# Microprocessor1.net
KiCad netlist of a schematic drawn in Altium Designer
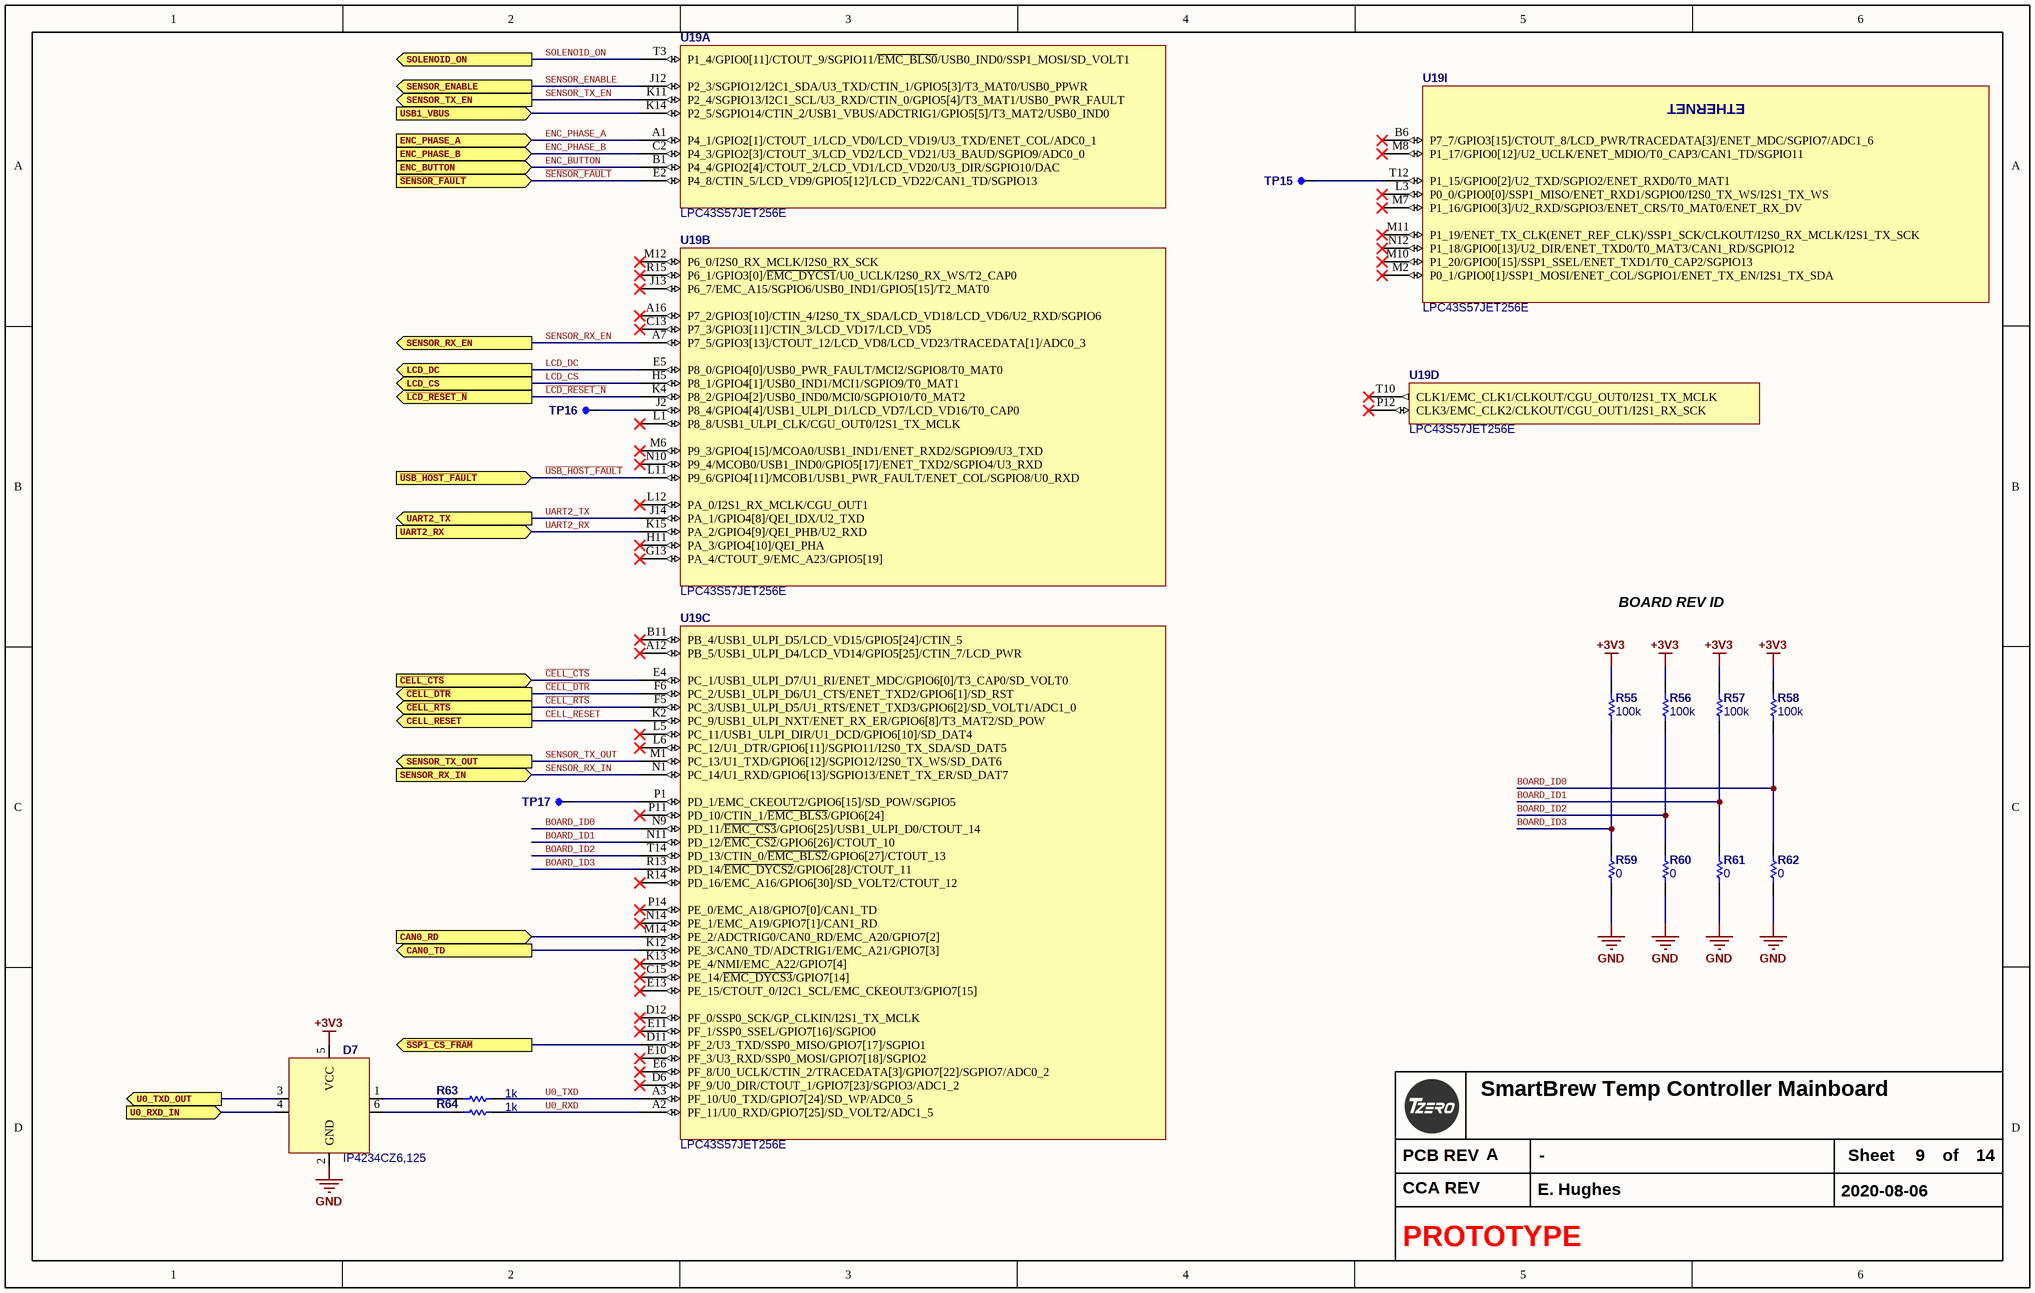
[diagram p0: Microprocessor1.SchDoc]

(export (version "E")
  (design (tool "Eeschema 10.0.6"))
  (components
    (comp (ref "D7")
      (value "IP4234CZ6,125")
      (footprint "SOT427_MEDIUM")
      (description "IC USB2.0 ESD PROTECTION SOT457")
      (fields (field (name "MANUFACTURER") "NXP Semiconductors"))
      (libsource (lib "Diodes-N") (part "IP4234CZ6,125"))
    )
    (comp (ref "R55")
      (value "100k")
      (footprint "R0603_0.55MM_MD")
      (description "RES 100K OHM 1/10W 1% 0603 SMD")
      (fields
        (field (name "MANUFACTURER PART NUMBER") "ERJ-3EKF1003V")
        (field (name "MANUFACTURER") "Panasonic Electronic Components")
      )
      (libsource (lib "Resistors - Panasonic - AEC-Q200") (part "R_2P"))
    )
    (comp (ref "R56")
      (value "100k")
      (footprint "R0603_0.55MM_MD")
      (description "RES 100K OHM 1/10W 1% 0603 SMD")
      (fields
        (field (name "MANUFACTURER PART NUMBER") "ERJ-3EKF1003V")
        (field (name "MANUFACTURER") "Panasonic Electronic Components")
      )
      (libsource (lib "Resistors - Panasonic - AEC-Q200") (part "R_2P"))
    )
    (comp (ref "R57")
      (value "100k")
      (footprint "R0603_0.55MM_MD")
      (description "RES 100K OHM 1/10W 1% 0603 SMD")
      (fields
        (field (name "MANUFACTURER PART NUMBER") "ERJ-3EKF1003V")
        (field (name "MANUFACTURER") "Panasonic Electronic Components")
      )
      (libsource (lib "Resistors - Panasonic - AEC-Q200") (part "R_2P"))
    )
    (comp (ref "R58")
      (value "100k")
      (footprint "R0603_0.55MM_MD")
      (description "RES 100K OHM 1/10W 1% 0603 SMD")
      (fields
        (field (name "MANUFACTURER PART NUMBER") "ERJ-3EKF1003V")
        (field (name "MANUFACTURER") "Panasonic Electronic Components")
      )
      (libsource (lib "Resistors - Panasonic - AEC-Q200") (part "R_2P"))
    )
    (comp (ref "R59")
      (value "0")
      (footprint "R0603_0.55MM_MD")
      (description "RES 0.0 OHM 1/10W JUMP 0603 SMD")
      (fields
        (field (name "MANUFACTURER") "Panasonic Electronic Components")
        (field (name "MANUFACTURER PART NUMBER") "ERJ-3GEY0R00V")
      )
      (libsource (lib "Resistors - Panasonic - AEC-Q200") (part "R_2P"))
    )
    (comp (ref "R60")
      (value "0")
      (footprint "R0603_0.55MM_MD")
      (description "RES 0.0 OHM 1/10W JUMP 0603 SMD")
      (fields
        (field (name "MANUFACTURER") "Panasonic Electronic Components")
        (field (name "MANUFACTURER PART NUMBER") "ERJ-3GEY0R00V")
      )
      (libsource (lib "Resistors - Panasonic - AEC-Q200") (part "R_2P"))
    )
    (comp (ref "R61")
      (value "0")
      (footprint "R0603_0.55MM_MD")
      (description "RES 0.0 OHM 1/10W JUMP 0603 SMD")
      (fields
        (field (name "MANUFACTURER") "Panasonic Electronic Components")
        (field (name "MANUFACTURER PART NUMBER") "ERJ-3GEY0R00V")
      )
      (libsource (lib "Resistors - Panasonic - AEC-Q200") (part "R_2P"))
    )
    (comp (ref "R62")
      (value "0")
      (footprint "R0603_0.55MM_MD")
      (description "RES 0.0 OHM 1/10W JUMP 0603 SMD")
      (fields
        (field (name "MANUFACTURER") "Panasonic Electronic Components")
        (field (name "MANUFACTURER PART NUMBER") "ERJ-3GEY0R00V")
      )
      (libsource (lib "Resistors - Panasonic - AEC-Q200") (part "R_2P"))
    )
    (comp (ref "R63")
      (value "1k")
      (footprint "R0603_0.55MM_MD")
      (description "RES 1K OHM 1/10W 1% 0603 SMD")
      (fields
        (field (name "MANUFACTURER PART NUMBER") "ERJ-3EKF1001V")
        (field (name "MANUFACTURER") "Panasonic Electronic Components")
      )
      (libsource (lib "Resistors - Panasonic - AEC-Q200") (part "R_2P"))
    )
    (comp (ref "R64")
      (value "1k")
      (footprint "R0603_0.55MM_MD")
      (description "RES 1K OHM 1/10W 1% 0603 SMD")
      (fields
        (field (name "MANUFACTURER PART NUMBER") "ERJ-3EKF1001V")
        (field (name "MANUFACTURER") "Panasonic Electronic Components")
      )
      (libsource (lib "Resistors - Panasonic - AEC-Q200") (part "R_2P"))
    )
    (comp (ref "TP15")
      (value "~")
      (footprint "TP_SMT_25_MIL_ROUND")
      (libsource (lib "Test Points-N") (part "TP SMT 25MIL"))
    )
    (comp (ref "TP16")
      (value "~")
      (footprint "TP_SMT_25_MIL_ROUND")
      (libsource (lib "Test Points-N") (part "TP SMT 25MIL"))
    )
    (comp (ref "TP17")
      (value "~")
      (footprint "TP_SMT_25_MIL_ROUND")
      (libsource (lib "Test Points-N") (part "TP SMT 25MIL"))
    )
    (comp (ref "U19")
      (value "LPC43S57JET256E")
      (footprint "Integrated Circuits BGA-N:LBGA256 16X16 1700X1700X155")
      (description "ARM Microcontrollers - MCU CortexM0/4 32bit 1MB Cortex-M4/M0")
      (fields (field (name "MANUFACTURER") "NXP Semiconductors"))
      (libsource (lib "eIC") (part "LPC43S57JET256E"))
    )
  )
  (nets
    (net (code "1") (name "+3V3") (class "Default")
      (node (ref "D7") (pin "5") (pinfunction "VCC_5") (pintype "passive"))
      (node (ref "R55") (pin "1") (pinfunction "1_1") (pintype "passive"))
      (node (ref "R56") (pin "1") (pinfunction "1_1") (pintype "passive"))
      (node (ref "R57") (pin "1") (pinfunction "1_1") (pintype "passive"))
      (node (ref "R58") (pin "1") (pinfunction "1_1") (pintype "passive"))
    )
    (net (code "2") (name "/BOARD_ID0") (class "Default")
      (node (ref "R58") (pin "2") (pinfunction "2_2") (pintype "passive"))
      (node (ref "R62") (pin "1") (pinfunction "1_1") (pintype "passive"))
      (node (ref "U19") (pin "N9") (pinfunction "PD_11/~{EMC_CS3}/GPIO6[25]/USB1_ULPI_D0/CTOUT_14_N9") (pintype "bidirectional"))
    )
    (net (code "3") (name "/BOARD_ID1") (class "Default")
      (node (ref "R57") (pin "2") (pinfunction "2_2") (pintype "passive"))
      (node (ref "R61") (pin "1") (pinfunction "1_1") (pintype "passive"))
      (node (ref "U19") (pin "N11") (pinfunction "PD_12/~{EMC_CS2}/GPIO6[26]/CTOUT_10_N11") (pintype "bidirectional"))
    )
    (net (code "4") (name "/BOARD_ID2") (class "Default")
      (node (ref "R56") (pin "2") (pinfunction "2_2") (pintype "passive"))
      (node (ref "R60") (pin "1") (pinfunction "1_1") (pintype "passive"))
      (node (ref "U19") (pin "T14") (pinfunction "PD_13/CTIN_0/~{EMC_BLS2}/GPIO6[27]/CTOUT_13_T14") (pintype "bidirectional"))
    )
    (net (code "5") (name "/BOARD_ID3") (class "Default")
      (node (ref "R55") (pin "2") (pinfunction "2_2") (pintype "passive"))
      (node (ref "R59") (pin "1") (pinfunction "1_1") (pintype "passive"))
      (node (ref "U19") (pin "R13") (pinfunction "PD_14/~{EMC_DYCS2}/GPIO6[28]/CTOUT_11_R13") (pintype "bidirectional"))
    )
    (net (code "6") (name "/CAN0_RD") (class "Default")
      (node (ref "U19") (pin "M14") (pinfunction "PE_2/ADCTRIG0/CAN0_RD/EMC_A20/GPIO7[2]_M14") (pintype "bidirectional"))
    )
    (net (code "7") (name "/CAN0_TD") (class "Default")
      (node (ref "U19") (pin "K12") (pinfunction "PE_3/CAN0_TD/ADCTRIG1/EMC_A21/GPIO7[3]_K12") (pintype "bidirectional"))
    )
    (net (code "8") (name "/CELL_CTS") (class "Default")
      (node (ref "U19") (pin "E4") (pinfunction "PC_1/USB1_ULPI_D7/U1_RI/ENET_MDC/GPIO6[0]/T3_CAP0/SD_VOLT0_E4") (pintype "bidirectional"))
    )
    (net (code "9") (name "/CELL_DTR") (class "Default")
      (node (ref "U19") (pin "F6") (pinfunction "PC_2/USB1_ULPI_D6/U1_CTS/ENET_TXD2/GPIO6[1]/SD_RST_F6") (pintype "bidirectional"))
    )
    (net (code "10") (name "/CELL_RESET") (class "Default")
      (node (ref "U19") (pin "K2") (pinfunction "PC_9/USB1_ULPI_NXT/ENET_RX_ER/GPIO6[8]/T3_MAT2/SD_POW_K2") (pintype "bidirectional"))
    )
    (net (code "11") (name "/CELL_RTS") (class "Default")
      (node (ref "U19") (pin "F5") (pinfunction "PC_3/USB1_ULPI_D5/U1_RTS/ENET_TXD3/GPIO6[2]/SD_VOLT1/ADC1_0_F5") (pintype "bidirectional"))
    )
    (net (code "12") (name "/ENC_BUTTON") (class "Default")
      (node (ref "U19") (pin "B1") (pinfunction "P4_4/GPIO2[4]/CTOUT_2/LCD_VD1/LCD_VD20/U3_DIR/SGPIO10/DAC_B1") (pintype "bidirectional"))
    )
    (net (code "13") (name "/ENC_PHASE_A") (class "Default")
      (node (ref "U19") (pin "A1") (pinfunction "P4_1/GPIO2[1]/CTOUT_1/LCD_VD0/LCD_VD19/U3_TXD/ENET_COL/ADC0_1_A1") (pintype "bidirectional"))
    )
    (net (code "14") (name "/ENC_PHASE_B") (class "Default")
      (node (ref "U19") (pin "C2") (pinfunction "P4_3/GPIO2[3]/CTOUT_3/LCD_VD2/LCD_VD21/U3_BAUD/SGPIO9/ADC0_0_C2") (pintype "bidirectional"))
    )
    (net (code "15") (name "/LCD_CS") (class "Default")
      (node (ref "U19") (pin "H5") (pinfunction "P8_1/GPIO4[1]/USB0_IND1/MCI1/SGPIO9/T0_MAT1_H5") (pintype "bidirectional"))
    )
    (net (code "16") (name "/LCD_DC") (class "Default")
      (node (ref "U19") (pin "E5") (pinfunction "P8_0/GPIO4[0]/USB0_PWR_FAULT/MCI2/SGPIO8/T0_MAT0_E5") (pintype "bidirectional"))
    )
    (net (code "17") (name "/LCD_RESET_N") (class "Default")
      (node (ref "U19") (pin "K4") (pinfunction "P8_2/GPIO4[2]/USB0_IND0/MCI0/SGPIO10/T0_MAT2_K4") (pintype "bidirectional"))
    )
    (net (code "18") (name "/SENSOR_ENABLE") (class "Default")
      (node (ref "U19") (pin "J12") (pinfunction "P2_3/SGPIO12/I2C1_SDA/U3_TXD/CTIN_1/GPIO5[3]/T3_MAT0/USB0_PPWR_J12") (pintype "bidirectional"))
    )
    (net (code "19") (name "/SENSOR_FAULT") (class "Default")
      (node (ref "U19") (pin "E2") (pinfunction "P4_8/CTIN_5/LCD_VD9/GPIO5[12]/LCD_VD22/CAN1_TD/SGPIO13_E2") (pintype "bidirectional"))
    )
    (net (code "20") (name "/SENSOR_RX_EN") (class "Default")
      (node (ref "U19") (pin "A7") (pinfunction "P7_5/GPIO3[13]/CTOUT_12/LCD_VD8/LCD_VD23/TRACEDATA[1]/ADC0_3_A7") (pintype "bidirectional"))
    )
    (net (code "21") (name "/SENSOR_RX_IN") (class "Default")
      (node (ref "U19") (pin "N1") (pinfunction "PC_14/U1_RXD/GPIO6[13]/SGPIO13/ENET_TX_ER/SD_DAT7_N1") (pintype "bidirectional"))
    )
    (net (code "22") (name "/SENSOR_TX_EN") (class "Default")
      (node (ref "U19") (pin "K11") (pinfunction "P2_4/SGPIO13/I2C1_SCL/U3_RXD/CTIN_0/GPIO5[4]/T3_MAT1/USB0_PWR_FAULT_K11") (pintype "bidirectional"))
    )
    (net (code "23") (name "/SENSOR_TX_OUT") (class "Default")
      (node (ref "U19") (pin "M1") (pinfunction "PC_13/U1_TXD/GPIO6[12]/SGPIO12/I2S0_TX_WS/SD_DAT6_M1") (pintype "bidirectional"))
    )
    (net (code "24") (name "/SOLENOID_ON") (class "Default")
      (node (ref "U19") (pin "T3") (pinfunction "P1_4/GPIO0[11]/CTOUT_9/SGPIO11/~{EMC_BLS0}/USB0_IND0/SSP1_MOSI/SD_VOLT1_T3") (pintype "bidirectional"))
    )
    (net (code "25") (name "/SSP1_CS_FRAM") (class "Default")
      (node (ref "U19") (pin "D11") (pinfunction "PF_2/U3_TXD/SSP0_MISO/GPIO7[17]/SGPIO1_D11") (pintype "bidirectional"))
    )
    (net (code "26") (name "/U0_RXD") (class "Default")
      (node (ref "R64") (pin "2") (pinfunction "2_2") (pintype "passive"))
      (node (ref "U19") (pin "A2") (pinfunction "PF_11/U0_RXD/GPIO7[25]/SD_VOLT2/ADC1_5_A2") (pintype "bidirectional"))
    )
    (net (code "27") (name "/U0_RXD_IN") (class "Default")
      (node (ref "D7") (pin "4") (pinfunction "4_4") (pintype "passive"))
    )
    (net (code "28") (name "/U0_TXD") (class "Default")
      (node (ref "R63") (pin "2") (pinfunction "2_2") (pintype "passive"))
      (node (ref "U19") (pin "A3") (pinfunction "PF_10/U0_TXD/GPIO7[24]/SD_WP/ADC0_5_A3") (pintype "bidirectional"))
    )
    (net (code "29") (name "/U0_TXD_OUT") (class "Default")
      (node (ref "D7") (pin "3") (pinfunction "3_3") (pintype "passive"))
    )
    (net (code "30") (name "/UART2_RX") (class "Default")
      (node (ref "U19") (pin "K15") (pinfunction "PA_2/GPIO4[9]/QEI_PHB/U2_RXD_K15") (pintype "bidirectional"))
    )
    (net (code "31") (name "/UART2_TX") (class "Default")
      (node (ref "U19") (pin "J14") (pinfunction "PA_1/GPIO4[8]/QEI_IDX/U2_TXD_J14") (pintype "bidirectional"))
    )
    (net (code "32") (name "/USB1_VBUS") (class "Default")
      (node (ref "U19") (pin "K14") (pinfunction "P2_5/SGPIO14/CTIN_2/USB1_VBUS/ADCTRIG1/GPIO5[5]/T3_MAT2/USB0_IND0_K14") (pintype "bidirectional"))
    )
    (net (code "33") (name "/USB_HOST_FAULT") (class "Default")
      (node (ref "U19") (pin "L11") (pinfunction "P9_6/GPIO4[11]/MCOB1/USB1_PWR_FAULT/ENET_COL/SGPIO8/U0_RXD_L11") (pintype "bidirectional"))
    )
    (net (code "34") (name "GND") (class "Default")
      (node (ref "D7") (pin "2") (pinfunction "GND_2") (pintype "passive"))
      (node (ref "R59") (pin "2") (pinfunction "2_2") (pintype "passive"))
      (node (ref "R60") (pin "2") (pinfunction "2_2") (pintype "passive"))
      (node (ref "R61") (pin "2") (pinfunction "2_2") (pintype "passive"))
      (node (ref "R62") (pin "2") (pinfunction "2_2") (pintype "passive"))
    )
    (net (code "35") (name "Net-(D7-Pad1)") (class "Default")
      (node (ref "D7") (pin "1") (pinfunction "1_1") (pintype "passive"))
      (node (ref "R63") (pin "1") (pinfunction "1_1") (pintype "passive"))
    )
    (net (code "36") (name "Net-(D7-Pad6)") (class "Default")
      (node (ref "D7") (pin "6") (pinfunction "6_6") (pintype "passive"))
      (node (ref "R64") (pin "1") (pinfunction "1_1") (pintype "passive"))
    )
    (net (code "37") (name "Net-(U19B-P8_4{slash}GPIO4[4]{slash}USB1_ULPI_D1{slash}LCD_VD7{slash}LCD_VD16{slash}T0_CAP0)") (class "Default")
      (node (ref "TP16") (pin "1") (pinfunction "1_1") (pintype "passive"))
      (node (ref "U19") (pin "J2") (pinfunction "P8_4/GPIO4[4]/USB1_ULPI_D1/LCD_VD7/LCD_VD16/T0_CAP0_J2") (pintype "bidirectional"))
    )
    (net (code "38") (name "Net-(U19C-PD_1{slash}EMC_CKEOUT2{slash}GPIO6[15]{slash}SD_POW{slash}SGPIO5)") (class "Default")
      (node (ref "TP17") (pin "1") (pinfunction "1_1") (pintype "passive"))
      (node (ref "U19") (pin "P1") (pinfunction "PD_1/EMC_CKEOUT2/GPIO6[15]/SD_POW/SGPIO5_P1") (pintype "bidirectional"))
    )
    (net (code "39") (name "Net-(U19I-P1_15{slash}GPIO0[2]{slash}U2_TXD{slash}SGPIO2{slash}ENET_RXD0{slash}T0_MAT1)") (class "Default")
      (node (ref "TP15") (pin "1") (pinfunction "1_1") (pintype "passive"))
      (node (ref "U19") (pin "T12") (pinfunction "P1_15/GPIO0[2]/U2_TXD/SGPIO2/ENET_RXD0/T0_MAT1_T12") (pintype "bidirectional"))
    )
    (net (code "40") (name "unconnected-(U19B-P6_0{slash}I2S0_RX_MCLK{slash}I2S0_RX_SCK-PadM12)") (class "Default")
      (node (ref "U19") (pin "M12") (pinfunction "P6_0/I2S0_RX_MCLK/I2S0_RX_SCK_M12") (pintype "bidirectional+no_connect"))
    )
    (net (code "41") (name "unconnected-(U19B-P6_1{slash}GPIO3[0]{slash}~{EMC_DYCS1}{slash}U0_UCLK{slash}I2S0_RX_WS{slash}T2_CAP0-PadR15)") (class "Default")
      (node (ref "U19") (pin "R15") (pinfunction "P6_1/GPIO3[0]/~{EMC_DYCS1}/U0_UCLK/I2S0_RX_WS/T2_CAP0_R15") (pintype "bidirectional+no_connect"))
    )
    (net (code "42") (name "unconnected-(U19B-P6_7{slash}EMC_A15{slash}SGPIO6{slash}USB0_IND1{slash}GPIO5[15]{slash}T2_MAT0-PadJ13)") (class "Default")
      (node (ref "U19") (pin "J13") (pinfunction "P6_7/EMC_A15/SGPIO6/USB0_IND1/GPIO5[15]/T2_MAT0_J13") (pintype "bidirectional+no_connect"))
    )
    (net (code "43") (name "unconnected-(U19B-P7_2{slash}GPIO3[10]{slash}CTIN_4{slash}I2S0_TX_SDA{slash}LCD_VD18{slash}LCD_VD6{slash}U2_RXD{slash}SGPIO6-PadA16)") (class "Default")
      (node (ref "U19") (pin "A16") (pinfunction "P7_2/GPIO3[10]/CTIN_4/I2S0_TX_SDA/LCD_VD18/LCD_VD6/U2_RXD/SGPIO6_A16") (pintype "bidirectional+no_connect"))
    )
    (net (code "44") (name "unconnected-(U19B-P7_3{slash}GPIO3[11]{slash}CTIN_3{slash}LCD_VD17{slash}LCD_VD5-PadC13)") (class "Default")
      (node (ref "U19") (pin "C13") (pinfunction "P7_3/GPIO3[11]/CTIN_3/LCD_VD17/LCD_VD5_C13") (pintype "bidirectional+no_connect"))
    )
    (net (code "45") (name "unconnected-(U19B-P8_8{slash}USB1_ULPI_CLK{slash}CGU_OUT0{slash}I2S1_TX_MCLK-PadL1)") (class "Default")
      (node (ref "U19") (pin "L1") (pinfunction "P8_8/USB1_ULPI_CLK/CGU_OUT0/I2S1_TX_MCLK_L1") (pintype "bidirectional+no_connect"))
    )
    (net (code "46") (name "unconnected-(U19B-P9_3{slash}GPIO4[15]{slash}MCOA0{slash}USB1_IND1{slash}ENET_RXD2{slash}SGPIO9{slash}U3_TXD-PadM6)") (class "Default")
      (node (ref "U19") (pin "M6") (pinfunction "P9_3/GPIO4[15]/MCOA0/USB1_IND1/ENET_RXD2/SGPIO9/U3_TXD_M6") (pintype "bidirectional+no_connect"))
    )
    (net (code "47") (name "unconnected-(U19B-P9_4{slash}MCOB0{slash}USB1_IND0{slash}GPIO5[17]{slash}ENET_TXD2{slash}SGPIO4{slash}U3_RXD-PadN10)") (class "Default")
      (node (ref "U19") (pin "N10") (pinfunction "P9_4/MCOB0/USB1_IND0/GPIO5[17]/ENET_TXD2/SGPIO4/U3_RXD_N10") (pintype "bidirectional+no_connect"))
    )
    (net (code "48") (name "unconnected-(U19B-PA_0{slash}I2S1_RX_MCLK{slash}CGU_OUT1-PadL12)") (class "Default")
      (node (ref "U19") (pin "L12") (pinfunction "PA_0/I2S1_RX_MCLK/CGU_OUT1_L12") (pintype "bidirectional+no_connect"))
    )
    (net (code "49") (name "unconnected-(U19B-PA_3{slash}GPIO4[10]{slash}QEI_PHA-PadH11)") (class "Default")
      (node (ref "U19") (pin "H11") (pinfunction "PA_3/GPIO4[10]/QEI_PHA_H11") (pintype "bidirectional+no_connect"))
    )
    (net (code "50") (name "unconnected-(U19B-PA_4{slash}CTOUT_9{slash}EMC_A23{slash}GPIO5[19]-PadG13)") (class "Default")
      (node (ref "U19") (pin "G13") (pinfunction "PA_4/CTOUT_9/EMC_A23/GPIO5[19]_G13") (pintype "bidirectional+no_connect"))
    )
    (net (code "51") (name "unconnected-(U19C-PB_4{slash}USB1_ULPI_D5{slash}LCD_VD15{slash}GPIO5[24]{slash}CTIN_5-PadB11)") (class "Default")
      (node (ref "U19") (pin "B11") (pinfunction "PB_4/USB1_ULPI_D5/LCD_VD15/GPIO5[24]/CTIN_5_B11") (pintype "bidirectional+no_connect"))
    )
    (net (code "52") (name "unconnected-(U19C-PB_5{slash}USB1_ULPI_D4{slash}LCD_VD14{slash}GPIO5[25]{slash}CTIN_7{slash}LCD_PWR-PadA12)") (class "Default")
      (node (ref "U19") (pin "A12") (pinfunction "PB_5/USB1_ULPI_D4/LCD_VD14/GPIO5[25]/CTIN_7/LCD_PWR_A12") (pintype "bidirectional+no_connect"))
    )
    (net (code "53") (name "unconnected-(U19C-PC_11{slash}USB1_ULPI_DIR{slash}U1_DCD{slash}GPIO6[10]{slash}SD_DAT4-PadL5)") (class "Default")
      (node (ref "U19") (pin "L5") (pinfunction "PC_11/USB1_ULPI_DIR/U1_DCD/GPIO6[10]/SD_DAT4_L5") (pintype "bidirectional+no_connect"))
    )
    (net (code "54") (name "unconnected-(U19C-PC_12{slash}U1_DTR{slash}GPIO6[11]{slash}SGPIO11{slash}I2S0_TX_SDA{slash}SD_DAT5-PadL6)") (class "Default")
      (node (ref "U19") (pin "L6") (pinfunction "PC_12/U1_DTR/GPIO6[11]/SGPIO11/I2S0_TX_SDA/SD_DAT5_L6") (pintype "bidirectional+no_connect"))
    )
    (net (code "55") (name "unconnected-(U19C-PD_10{slash}CTIN_1{slash}~{EMC_BLS3}{slash}GPIO6[24]-PadP11)") (class "Default")
      (node (ref "U19") (pin "P11") (pinfunction "PD_10/CTIN_1/~{EMC_BLS3}/GPIO6[24]_P11") (pintype "bidirectional+no_connect"))
    )
    (net (code "56") (name "unconnected-(U19C-PD_16{slash}EMC_A16{slash}GPIO6[30]{slash}SD_VOLT2{slash}CTOUT_12-PadR14)") (class "Default")
      (node (ref "U19") (pin "R14") (pinfunction "PD_16/EMC_A16/GPIO6[30]/SD_VOLT2/CTOUT_12_R14") (pintype "bidirectional+no_connect"))
    )
    (net (code "57") (name "unconnected-(U19C-PE_0{slash}EMC_A18{slash}GPIO7[0]{slash}CAN1_TD-PadP14)") (class "Default")
      (node (ref "U19") (pin "P14") (pinfunction "PE_0/EMC_A18/GPIO7[0]/CAN1_TD_P14") (pintype "bidirectional+no_connect"))
    )
    (net (code "58") (name "unconnected-(U19C-PE_1{slash}EMC_A19{slash}GPIO7[1]{slash}CAN1_RD-PadN14)") (class "Default")
      (node (ref "U19") (pin "N14") (pinfunction "PE_1/EMC_A19/GPIO7[1]/CAN1_RD_N14") (pintype "bidirectional+no_connect"))
    )
    (net (code "59") (name "unconnected-(U19C-PE_4{slash}NMI{slash}EMC_A22{slash}GPIO7[4]-PadK13)") (class "Default")
      (node (ref "U19") (pin "K13") (pinfunction "PE_4/NMI/EMC_A22/GPIO7[4]_K13") (pintype "bidirectional+no_connect"))
    )
    (net (code "60") (name "unconnected-(U19C-PE_14{slash}~{EMC_DYCS3}{slash}GPIO7[14]-PadC15)") (class "Default")
      (node (ref "U19") (pin "C15") (pinfunction "PE_14/~{EMC_DYCS3}/GPIO7[14]_C15") (pintype "bidirectional+no_connect"))
    )
    (net (code "61") (name "unconnected-(U19C-PE_15{slash}CTOUT_0{slash}I2C1_SCL{slash}EMC_CKEOUT3{slash}GPIO7[15]-PadE13)") (class "Default")
      (node (ref "U19") (pin "E13") (pinfunction "PE_15/CTOUT_0/I2C1_SCL/EMC_CKEOUT3/GPIO7[15]_E13") (pintype "bidirectional+no_connect"))
    )
    (net (code "62") (name "unconnected-(U19C-PF_0{slash}SSP0_SCK{slash}GP_CLKIN{slash}I2S1_TX_MCLK-PadD12)") (class "Default")
      (node (ref "U19") (pin "D12") (pinfunction "PF_0/SSP0_SCK/GP_CLKIN/I2S1_TX_MCLK_D12") (pintype "bidirectional+no_connect"))
    )
    (net (code "63") (name "unconnected-(U19C-PF_1{slash}SSP0_SSEL{slash}GPIO7[16]{slash}SGPIO0-PadE11)") (class "Default")
      (node (ref "U19") (pin "E11") (pinfunction "PF_1/SSP0_SSEL/GPIO7[16]/SGPIO0_E11") (pintype "bidirectional+no_connect"))
    )
    (net (code "64") (name "unconnected-(U19C-PF_3{slash}U3_RXD{slash}SSP0_MOSI{slash}GPIO7[18]{slash}SGPIO2-PadE10)") (class "Default")
      (node (ref "U19") (pin "E10") (pinfunction "PF_3/U3_RXD/SSP0_MOSI/GPIO7[18]/SGPIO2_E10") (pintype "bidirectional+no_connect"))
    )
    (net (code "65") (name "unconnected-(U19C-PF_8{slash}U0_UCLK{slash}CTIN_2{slash}TRACEDATA[3]{slash}GPIO7[22]{slash}SGPIO7{slash}ADC0_2-PadE6)") (class "Default")
      (node (ref "U19") (pin "E6") (pinfunction "PF_8/U0_UCLK/CTIN_2/TRACEDATA[3]/GPIO7[22]/SGPIO7/ADC0_2_E6") (pintype "bidirectional+no_connect"))
    )
    (net (code "66") (name "unconnected-(U19C-PF_9{slash}U0_DIR{slash}CTOUT_1{slash}GPIO7[23]{slash}SGPIO3{slash}ADC1_2-PadD6)") (class "Default")
      (node (ref "U19") (pin "D6") (pinfunction "PF_9/U0_DIR/CTOUT_1/GPIO7[23]/SGPIO3/ADC1_2_D6") (pintype "bidirectional+no_connect"))
    )
    (net (code "67") (name "unconnected-(U19D-CLK1{slash}EMC_CLK1{slash}CLKOUT{slash}CGU_OUT0{slash}I2S1_TX_MCLK-PadT10)") (class "Default")
      (node (ref "U19") (pin "T10") (pinfunction "CLK1/EMC_CLK1/CLKOUT/CGU_OUT0/I2S1_TX_MCLK_T10") (pintype "output+no_connect"))
    )
    (net (code "68") (name "unconnected-(U19D-CLK3{slash}EMC_CLK2{slash}CLKOUT{slash}CGU_OUT1{slash}I2S1_RX_SCK-PadP12)") (class "Default")
      (node (ref "U19") (pin "P12") (pinfunction "CLK3/EMC_CLK2/CLKOUT/CGU_OUT1/I2S1_RX_SCK_P12") (pintype "bidirectional+no_connect"))
    )
    (net (code "69") (name "unconnected-(U19I-P0_0{slash}GPIO0[0]{slash}SSP1_MISO{slash}ENET_RXD1{slash}SGPIO0{slash}I2S0_TX_WS{slash}I2S1_TX_WS-PadL3)") (class "Default")
      (node (ref "U19") (pin "L3") (pinfunction "P0_0/GPIO0[0]/SSP1_MISO/ENET_RXD1/SGPIO0/I2S0_TX_WS/I2S1_TX_WS_L3") (pintype "bidirectional+no_connect"))
    )
    (net (code "70") (name "unconnected-(U19I-P0_1{slash}GPIO0[1]{slash}SSP1_MOSI{slash}ENET_COL{slash}SGPIO1{slash}ENET_TX_EN{slash}I2S1_TX_SDA-PadM2)") (class "Default")
      (node (ref "U19") (pin "M2") (pinfunction "P0_1/GPIO0[1]/SSP1_MOSI/ENET_COL/SGPIO1/ENET_TX_EN/I2S1_TX_SDA_M2") (pintype "bidirectional+no_connect"))
    )
    (net (code "71") (name "unconnected-(U19I-P1_16{slash}GPIO0[3]{slash}U2_RXD{slash}SGPIO3{slash}ENET_CRS{slash}T0_MAT0{slash}ENET_RX_DV-PadM7)") (class "Default")
      (node (ref "U19") (pin "M7") (pinfunction "P1_16/GPIO0[3]/U2_RXD/SGPIO3/ENET_CRS/T0_MAT0/ENET_RX_DV_M7") (pintype "bidirectional+no_connect"))
    )
    (net (code "72") (name "unconnected-(U19I-P1_17{slash}GPIO0[12]{slash}U2_UCLK{slash}ENET_MDIO{slash}T0_CAP3{slash}CAN1_TD{slash}SGPIO11-PadM8)") (class "Default")
      (node (ref "U19") (pin "M8") (pinfunction "P1_17/GPIO0[12]/U2_UCLK/ENET_MDIO/T0_CAP3/CAN1_TD/SGPIO11_M8") (pintype "bidirectional+no_connect"))
    )
    (net (code "73") (name "unconnected-(U19I-P1_18{slash}GPIO0[13]{slash}U2_DIR{slash}ENET_TXD0{slash}T0_MAT3{slash}CAN1_RD{slash}SGPIO12-PadN12)") (class "Default")
      (node (ref "U19") (pin "N12") (pinfunction "P1_18/GPIO0[13]/U2_DIR/ENET_TXD0/T0_MAT3/CAN1_RD/SGPIO12_N12") (pintype "bidirectional+no_connect"))
    )
    (net (code "74") (name "unconnected-(U19I-P1_19{slash}ENET_TX_CLK(ENET_REF_CLK){slash}SSP1_SCK{slash}CLKOUT{slash}I2S0_RX_MCLK{slash}I2S1_TX_SCK-PadM11)") (class "Default")
      (node (ref "U19") (pin "M11") (pinfunction "P1_19/ENET_TX_CLK(ENET_REF_CLK)/SSP1_SCK/CLKOUT/I2S0_RX_MCLK/I2S1_TX_SCK_M11") (pintype "bidirectional+no_connect"))
    )
    (net (code "75") (name "unconnected-(U19I-P1_20{slash}GPIO0[15]{slash}SSP1_SSEL{slash}ENET_TXD1{slash}T0_CAP2{slash}SGPIO13-PadM10)") (class "Default")
      (node (ref "U19") (pin "M10") (pinfunction "P1_20/GPIO0[15]/SSP1_SSEL/ENET_TXD1/T0_CAP2/SGPIO13_M10") (pintype "bidirectional+no_connect"))
    )
    (net (code "76") (name "unconnected-(U19I-P7_7{slash}GPIO3[15]{slash}CTOUT_8{slash}LCD_PWR{slash}TRACEDATA[3]{slash}ENET_MDC{slash}SGPIO7{slash}ADC1_6-PadB6)") (class "Default")
      (node (ref "U19") (pin "B6") (pinfunction "P7_7/GPIO3[15]/CTOUT_8/LCD_PWR/TRACEDATA[3]/ENET_MDC/SGPIO7/ADC1_6_B6") (pintype "bidirectional+no_connect"))
    )
  )
)
